# Sheet4.net
KiCad netlist of a schematic drawn in Altium Designer
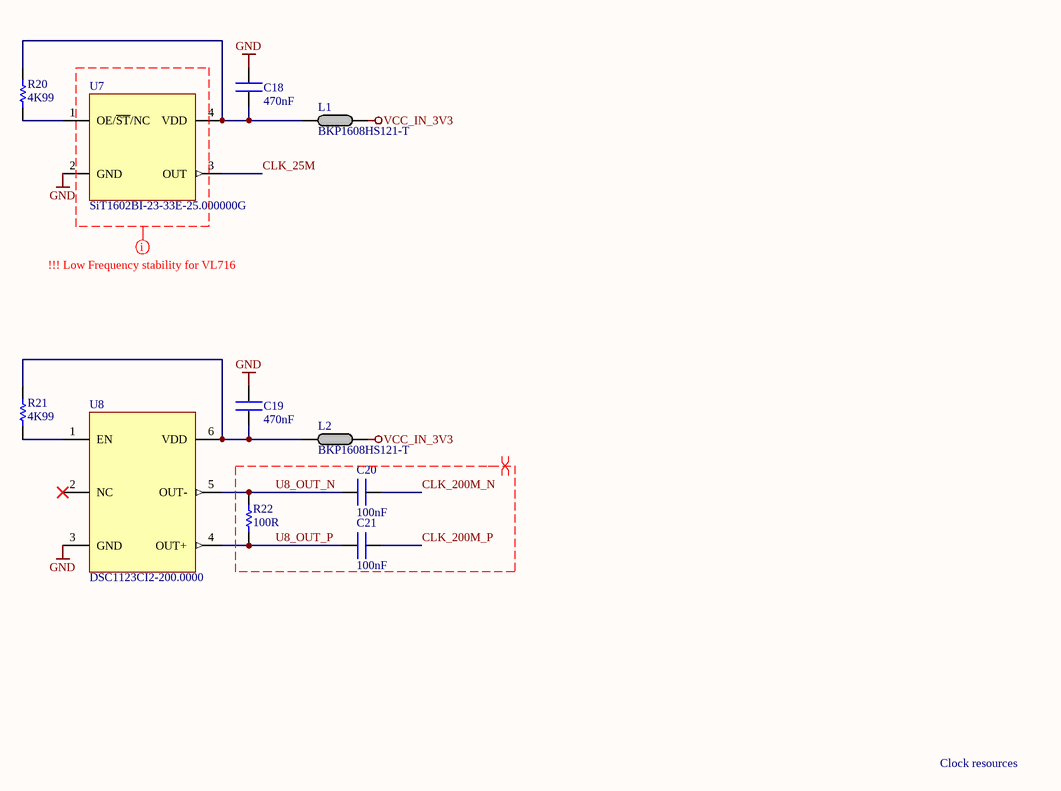
[diagram p0: Sheet4.SchDoc]

(export (version "E")
  (design (tool "Eeschema 10.0.6"))
  (components
    (comp (ref "C18")
      (value "470nF")
      (footprint "CAPC1005X05N")
      (description "Ceramic Chip Capacitor")
      (libsource (lib "Integrated_Library") (part "C0402"))
    )
    (comp (ref "C19")
      (value "470nF")
      (footprint "CAPC1005X05N")
      (description "Ceramic Chip Capacitor")
      (libsource (lib "Integrated_Library") (part "C0402"))
    )
    (comp (ref "C20")
      (value "100nF")
      (footprint "CAPC1005X05N")
      (description "Ceramic Chip Capacitor")
      (libsource (lib "Integrated_Library") (part "C0402"))
    )
    (comp (ref "C21")
      (value "100nF")
      (footprint "CAPC1005X05N")
      (description "Ceramic Chip Capacitor")
      (libsource (lib "Integrated_Library") (part "C0402"))
    )
    (comp (ref "L1")
      (value "BKP1608HS121-T")
      (footprint "INDC1608X08N")
      (description "MULTILAYER CHIP BEAD INDUCTOR FOR POWER LINES")
      (libsource (lib "Integrated_Library") (part "BKP1608HS121-T"))
    )
    (comp (ref "L2")
      (value "BKP1608HS121-T")
      (footprint "INDC1608X08N")
      (description "MULTILAYER CHIP BEAD INDUCTOR FOR POWER LINES")
      (libsource (lib "Integrated_Library") (part "BKP1608HS121-T"))
    )
    (comp (ref "R20")
      (value "4K99")
      (footprint "RESC1005X05N")
      (description "Ceramic Chip Resistor")
      (libsource (lib "Integrated_Library") (part "R0402"))
    )
    (comp (ref "R21")
      (value "4K99")
      (footprint "RESC1005X05N")
      (description "Ceramic Chip Resistor")
      (libsource (lib "Integrated_Library") (part "R0402"))
    )
    (comp (ref "R22")
      (value "100R")
      (footprint "RESC1005X05N")
      (description "Ceramic Chip Resistor")
      (libsource (lib "Integrated_Library") (part "R0402"))
    )
    (comp (ref "U7")
      (value "SiT1602BI-23-33E-25.000000G")
      (footprint "SiT1602BI-23-33E-25.000000G")
      (description "Low Power, Standard Frequency Oscillator")
      (libsource (lib "Integrated_Library") (part "SiT1602BI-23-33E-25.000000G"))
    )
    (comp (ref "U8")
      (value "DSC1123CI2-200.0000")
      (footprint "DSC1123CI2-200.0000")
      (description "Low-Jitter Precision LVDS Oscillator")
      (libsource (lib "Integrated_Library") (part "DSC1123CI2-200.0000"))
    )
  )
  (nets
    (net (code "1") (name "/CLK_25M") (class "Default")
      (node (ref "U7") (pin "3") (pinfunction "OUT_3") (pintype "output"))
    )
    (net (code "2") (name "/CLK_200M_N") (class "Default")
      (node (ref "C20") (pin "1") (pinfunction "1_1") (pintype "passive"))
    )
    (net (code "3") (name "/CLK_200M_P") (class "Default")
      (node (ref "C21") (pin "1") (pinfunction "1_1") (pintype "passive"))
    )
    (net (code "4") (name "/U8_OUT_N") (class "Default")
      (node (ref "C20") (pin "2") (pinfunction "2_2") (pintype "passive"))
      (node (ref "R22") (pin "1") (pinfunction "1_1") (pintype "passive"))
      (node (ref "U8") (pin "5") (pinfunction "OUT-_5") (pintype "output"))
    )
    (net (code "5") (name "/U8_OUT_P") (class "Default")
      (node (ref "C21") (pin "2") (pinfunction "2_2") (pintype "passive"))
      (node (ref "R22") (pin "2") (pinfunction "2_2") (pintype "passive"))
      (node (ref "U8") (pin "4") (pinfunction "OUT+_4") (pintype "output"))
    )
    (net (code "6") (name "GND") (class "Default")
      (node (ref "C18") (pin "2") (pinfunction "2_2") (pintype "passive"))
      (node (ref "C19") (pin "2") (pinfunction "2_2") (pintype "passive"))
      (node (ref "U7") (pin "2") (pinfunction "GND_2") (pintype "power_in"))
      (node (ref "U8") (pin "3") (pinfunction "GND_3") (pintype "power_in"))
    )
    (net (code "7") (name "Net-(U7-OE{slash}~{ST}{slash}NC)") (class "Default")
      (node (ref "R20") (pin "2") (pinfunction "2_2") (pintype "passive"))
      (node (ref "U7") (pin "1") (pinfunction "OE/~{ST}/NC_1") (pintype "passive"))
    )
    (net (code "8") (name "Net-(U7-VDD)") (class "Default")
      (node (ref "C18") (pin "1") (pinfunction "1_1") (pintype "passive"))
      (node (ref "L1") (pin "1") (pinfunction "1_1") (pintype "passive"))
      (node (ref "R20") (pin "1") (pinfunction "1_1") (pintype "passive"))
      (node (ref "U7") (pin "4") (pinfunction "VDD_4") (pintype "power_in"))
    )
    (net (code "9") (name "Net-(U8-EN)") (class "Default")
      (node (ref "R21") (pin "2") (pinfunction "2_2") (pintype "passive"))
      (node (ref "U8") (pin "1") (pinfunction "EN_1") (pintype "passive"))
    )
    (net (code "10") (name "Net-(U8-VDD)") (class "Default")
      (node (ref "C19") (pin "1") (pinfunction "1_1") (pintype "passive"))
      (node (ref "L2") (pin "1") (pinfunction "1_1") (pintype "passive"))
      (node (ref "R21") (pin "1") (pinfunction "1_1") (pintype "passive"))
      (node (ref "U8") (pin "6") (pinfunction "VDD_6") (pintype "power_in"))
    )
    (net (code "11") (name "VCC_IN_3V3") (class "Default")
      (node (ref "L1") (pin "2") (pinfunction "2_2") (pintype "passive"))
      (node (ref "L2") (pin "2") (pinfunction "2_2") (pintype "passive"))
    )
    (net (code "12") (name "unconnected-(U8-NC-Pad2)") (class "Default")
      (node (ref "U8") (pin "2") (pinfunction "NC_2") (pintype "passive+no_connect"))
    )
  )
)
